# common_emitter_se-punto_di_lavoro.net
KiCad netlist of a schematic drawn in EAGLE
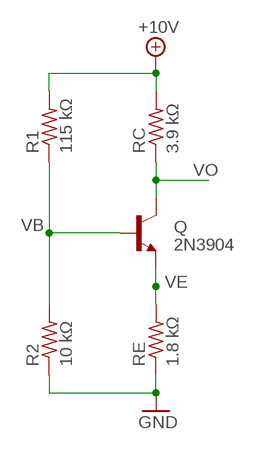
[diagram p0: schematic, sheet 1]

(export (version "E")
  (design (tool "Eeschema 10.0.6"))
  (components
    (comp (ref "Q")
      (value "2N3904")
      (footprint "eagle-import:TO92")
      (libsource (lib "eagle-import") (part "2N3904"))
    )
    (comp (ref "R1")
      (value "115 kΩ")
      (footprint "eagle-import:0204_5")
      (libsource (lib "eagle-import") (part "R-US_0204/5"))
    )
    (comp (ref "R2")
      (value "10 kΩ")
      (footprint "eagle-import:0204_5")
      (libsource (lib "eagle-import") (part "R-US_0204/5"))
    )
    (comp (ref "RC")
      (value "3.9 kΩ")
      (footprint "eagle-import:0204_5")
      (libsource (lib "eagle-import") (part "R-US_0204/5"))
    )
    (comp (ref "RE")
      (value "1.8 kΩ")
      (footprint "eagle-import:0204_5")
      (libsource (lib "eagle-import") (part "R-US_0204/5"))
    )
  )
  (nets
    (net (code "1") (name "+10V") (class "Default")
      (node (ref "R1") (pin "2") (pinfunction "2_2") (pintype "passive"))
      (node (ref "RC") (pin "2") (pinfunction "2_2") (pintype "passive"))
    )
    (net (code "2") (name "/VB") (class "Default")
      (node (ref "Q") (pin "2") (pinfunction "B_2") (pintype "passive"))
      (node (ref "R1") (pin "1") (pinfunction "1_1") (pintype "passive"))
      (node (ref "R2") (pin "2") (pinfunction "2_2") (pintype "passive"))
    )
    (net (code "3") (name "/VE") (class "Default")
      (node (ref "Q") (pin "3") (pinfunction "E_3") (pintype "passive"))
      (node (ref "RE") (pin "2") (pinfunction "2_2") (pintype "passive"))
    )
    (net (code "4") (name "/VO") (class "Default")
      (node (ref "Q") (pin "1") (pinfunction "C_1") (pintype "passive"))
      (node (ref "RC") (pin "1") (pinfunction "1_1") (pintype "passive"))
    )
    (net (code "5") (name "GND") (class "Default")
      (node (ref "R2") (pin "1") (pinfunction "1_1") (pintype "passive"))
      (node (ref "RE") (pin "1") (pinfunction "1_1") (pintype "passive"))
    )
  )
)
